# Muddi.net
KiCad netlist of a schematic drawn in EAGLE
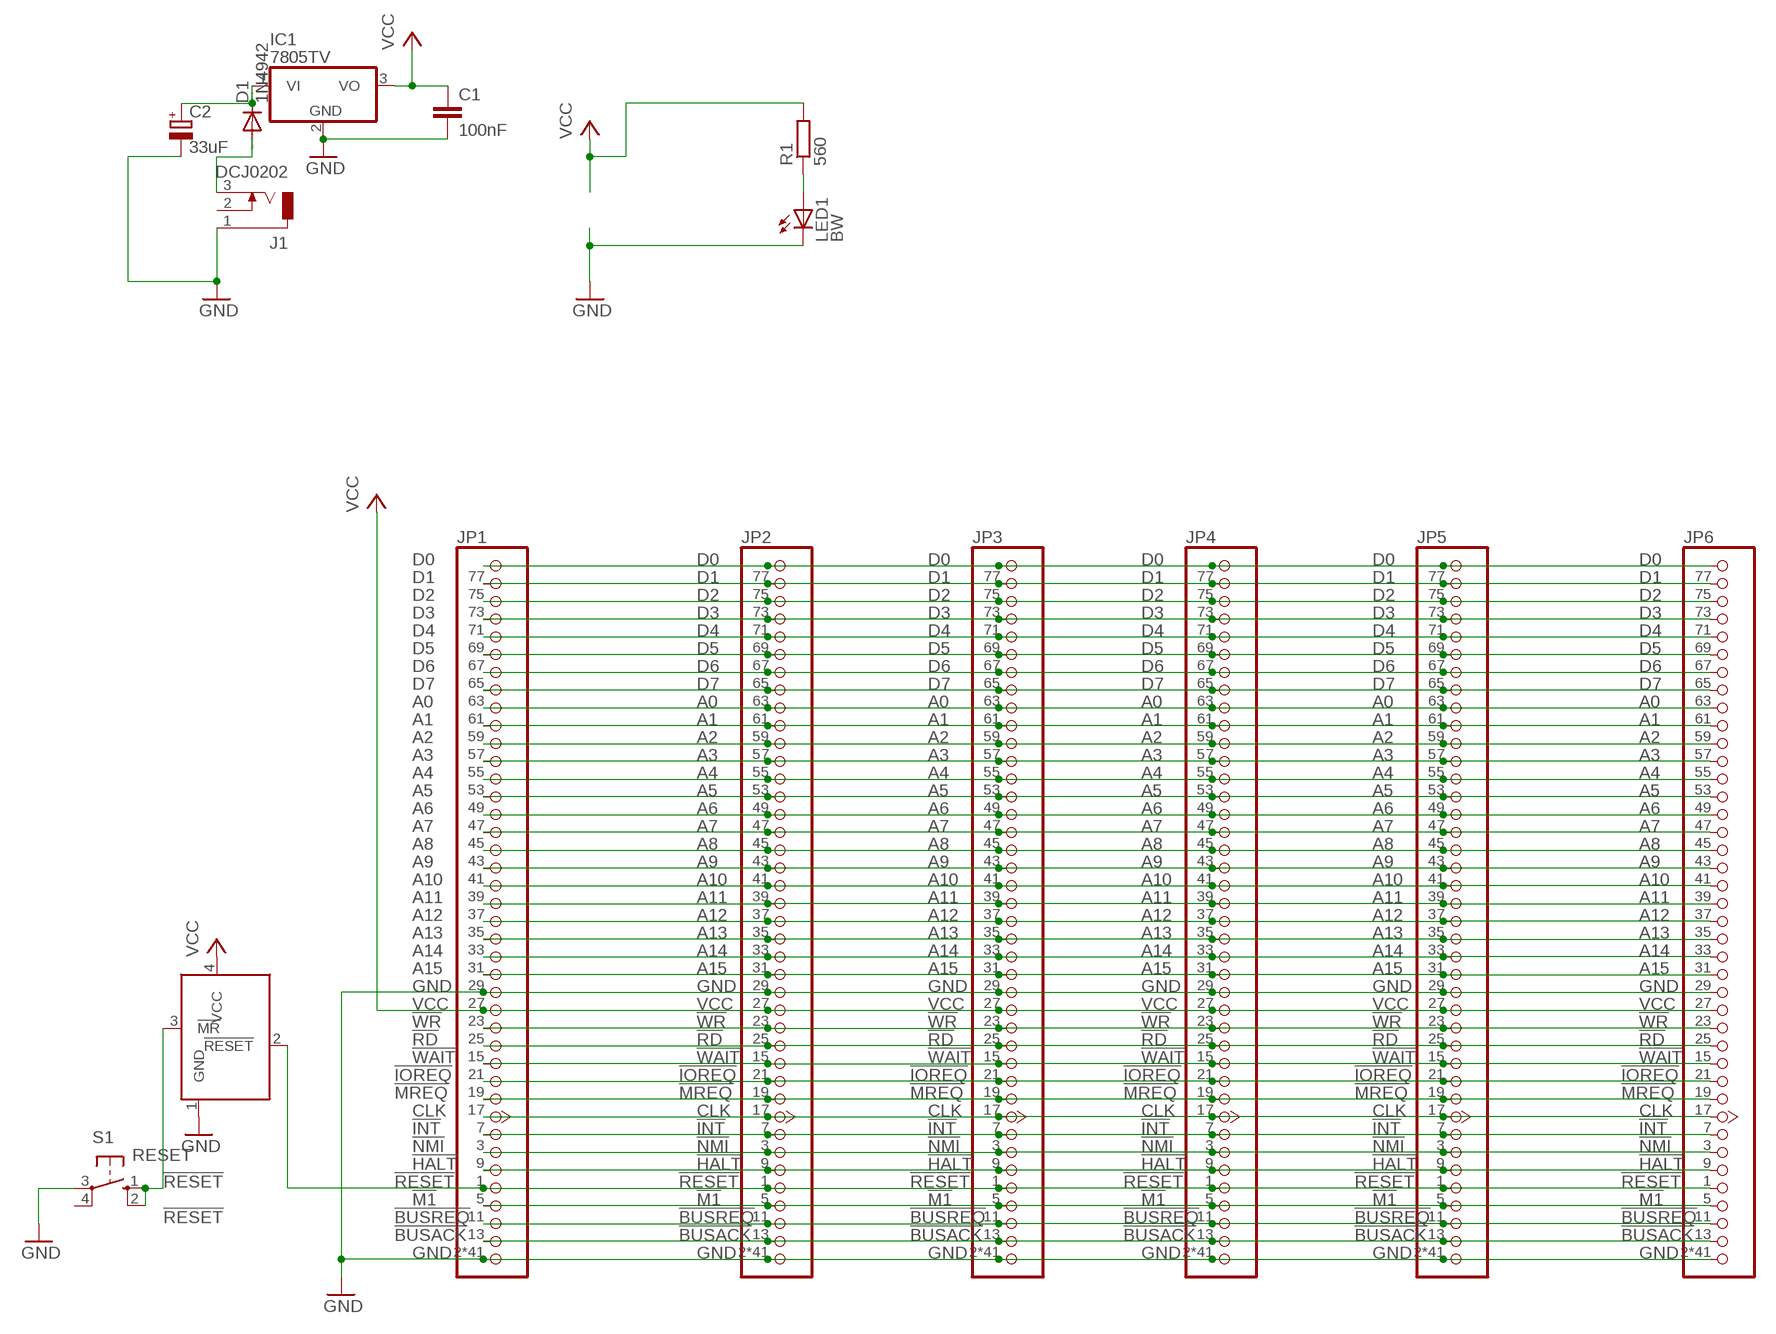
[diagram p0: schematic, sheet 1]

(export (version "E")
  (design (tool "Eeschema 10.0.6"))
  (components
    (comp (ref "C1")
      (value "100nF")
      (footprint "eagle-import:C2.5-2")
      (libsource (lib "eagle-import") (part "C2.5/2"))
    )
    (comp (ref "C2")
      (value "33uF")
      (footprint "eagle-import:E2,5-7")
      (libsource (lib "eagle-import") (part "CPOL-EUE2.5-7"))
    )
    (comp (ref "D1")
      (value "1N4942")
      (footprint "eagle-import:DO41-10")
      (fields (field (name "MF") "ON SEMICONDUCTOR") (field (name "MPN") "1N4935G"))
      (libsource (lib "eagle-import") (part "1N4942"))
    )
    (comp (ref "IC1")
      (value "7805TV")
      (footprint "eagle-import:TO220V")
      (libsource (lib "eagle-import") (part "78TV05"))
    )
    (comp (ref "J1")
      (value "DCJ0202")
      (footprint "eagle-import:DCJ0202")
      (libsource (lib "eagle-import") (part "DCJ0202"))
    )
    (comp (ref "JP1")
      (value "JEANNECTOR_57102-F08-25")
      (footprint "eagle-import:57102-F08-25")
      (libsource (lib "eagle-import") (part "JEANNECTOR_57102-F08-25"))
    )
    (comp (ref "JP2")
      (value "JEANNECTOR_57102-F08-25")
      (footprint "eagle-import:57102-F08-25")
      (libsource (lib "eagle-import") (part "JEANNECTOR_57102-F08-25"))
    )
    (comp (ref "JP3")
      (value "JEANNECTOR_57102-F08-25")
      (footprint "eagle-import:57102-F08-25")
      (libsource (lib "eagle-import") (part "JEANNECTOR_57102-F08-25"))
    )
    (comp (ref "JP4")
      (value "JEANNECTOR_57102-F08-25")
      (footprint "eagle-import:57102-F08-25")
      (libsource (lib "eagle-import") (part "JEANNECTOR_57102-F08-25"))
    )
    (comp (ref "JP5")
      (value "JEANNECTOR_57102-F08-25")
      (footprint "eagle-import:57102-F08-25")
      (libsource (lib "eagle-import") (part "JEANNECTOR_57102-F08-25"))
    )
    (comp (ref "JP6")
      (value "JEANNECTOR_57102-F08-25")
      (footprint "eagle-import:57102-F08-25")
      (libsource (lib "eagle-import") (part "JEANNECTOR_57102-F08-25"))
    )
    (comp (ref "LED1")
      (value "BW")
      (footprint "eagle-import:LED5MM")
      (libsource (lib "eagle-import") (part "LED5MM"))
    )
    (comp (ref "MAX811")
      (value "MAX811")
      (footprint "eagle-import:SOT143")
      (libsource (lib "eagle-import") (part "MAX811"))
    )
    (comp (ref "R1")
      (value "560")
      (footprint "eagle-import:0207_2V")
      (libsource (lib "eagle-import") (part "R-EU_0207/2V"))
    )
    (comp (ref "S1")
      (value "RESET")
      (footprint "eagle-import:B3F-10XX")
      (fields (field (name "MPN") "B3F-1000") (field (name "MF") "OMRON ELECTRONIC COMPONENTS"))
      (libsource (lib "eagle-import") (part "10-XX"))
    )
  )
  (nets
    (net (code "1") (name "/~{RESET}") (class "Default")
      (node (ref "MAX811") (pin "3") (pinfunction "~{MR}_3") (pintype "input"))
      (node (ref "S1") (pin "1") (pinfunction "S_1") (pintype "passive"))
      (node (ref "S1") (pin "2") (pinfunction "S1_2") (pintype "passive"))
    )
    (net (code "2") (name "GND") (class "Default")
      (node (ref "C1") (pin "2") (pinfunction "2_2") (pintype "passive"))
      (node (ref "C2") (pin "-") (pinfunction "-_-") (pintype "passive"))
      (node (ref "IC1") (pin "2") (pinfunction "GND_2") (pintype "passive"))
      (node (ref "J1") (pin "1") (pinfunction "1_1") (pintype "passive"))
      (node (ref "JP1") (pin "10") (pinfunction "GND_10") (pintype "power_in"))
      (node (ref "JP1") (pin "12") (pinfunction "GND_12") (pintype "power_in"))
      (node (ref "JP1") (pin "14") (pinfunction "GND_14") (pintype "power_in"))
      (node (ref "JP1") (pin "16") (pinfunction "GND_16") (pintype "power_in"))
      (node (ref "JP1") (pin "18") (pinfunction "GND_18") (pintype "power_in"))
      (node (ref "JP1") (pin "2") (pinfunction "GND_2") (pintype "power_in"))
      (node (ref "JP1") (pin "20") (pinfunction "GND_20") (pintype "power_in"))
      (node (ref "JP1") (pin "22") (pinfunction "GND_22") (pintype "power_in"))
      (node (ref "JP1") (pin "24") (pinfunction "GND_24") (pintype "power_in"))
      (node (ref "JP1") (pin "26") (pinfunction "GND_26") (pintype "power_in"))
      (node (ref "JP1") (pin "28") (pinfunction "GND_28") (pintype "power_in"))
      (node (ref "JP1") (pin "29") (pinfunction "GND_29") (pintype "power_in"))
      (node (ref "JP1") (pin "30") (pinfunction "GND_30") (pintype "power_in"))
      (node (ref "JP1") (pin "32") (pinfunction "GND_32") (pintype "power_in"))
      (node (ref "JP1") (pin "34") (pinfunction "GND_34") (pintype "power_in"))
      (node (ref "JP1") (pin "36") (pinfunction "GND_36") (pintype "power_in"))
      (node (ref "JP1") (pin "38") (pinfunction "GND_38") (pintype "power_in"))
      (node (ref "JP1") (pin "4") (pinfunction "GND_4") (pintype "power_in"))
      (node (ref "JP1") (pin "40") (pinfunction "GND_40") (pintype "power_in"))
      (node (ref "JP1") (pin "42") (pinfunction "GND_42") (pintype "power_in"))
      (node (ref "JP1") (pin "44") (pinfunction "GND_44") (pintype "power_in"))
      (node (ref "JP1") (pin "46") (pinfunction "GND_46") (pintype "power_in"))
      (node (ref "JP1") (pin "48") (pinfunction "GND_48") (pintype "power_in"))
      (node (ref "JP1") (pin "50") (pinfunction "GND_50") (pintype "power_in"))
      (node (ref "JP1") (pin "51") (pinfunction "GND_51") (pintype "power_in"))
      (node (ref "JP1") (pin "52") (pinfunction "GND_52") (pintype "power_in"))
      (node (ref "JP1") (pin "54") (pinfunction "GND_54") (pintype "power_in"))
      (node (ref "JP1") (pin "56") (pinfunction "GND_56") (pintype "power_in"))
      (node (ref "JP1") (pin "58") (pinfunction "GND_58") (pintype "power_in"))
      (node (ref "JP1") (pin "6") (pinfunction "GND_6") (pintype "power_in"))
      (node (ref "JP1") (pin "60") (pinfunction "GND_60") (pintype "power_in"))
      (node (ref "JP1") (pin "62") (pinfunction "GND_62") (pintype "power_in"))
      (node (ref "JP1") (pin "64") (pinfunction "GND_64") (pintype "power_in"))
      (node (ref "JP1") (pin "66") (pinfunction "GND_66") (pintype "power_in"))
      (node (ref "JP1") (pin "68") (pinfunction "GND_68") (pintype "power_in"))
      (node (ref "JP1") (pin "70") (pinfunction "GND_70") (pintype "power_in"))
      (node (ref "JP1") (pin "72") (pinfunction "GND_72") (pintype "power_in"))
      (node (ref "JP1") (pin "74") (pinfunction "GND_74") (pintype "power_in"))
      (node (ref "JP1") (pin "76") (pinfunction "GND_76") (pintype "power_in"))
      (node (ref "JP1") (pin "78") (pinfunction "GND_78") (pintype "power_in"))
      (node (ref "JP1") (pin "8") (pinfunction "GND_8") (pintype "power_in"))
      (node (ref "JP1") (pin "80") (pinfunction "GND_80") (pintype "power_in"))
      (node (ref "JP2") (pin "10") (pinfunction "GND_10") (pintype "power_in"))
      (node (ref "JP2") (pin "12") (pinfunction "GND_12") (pintype "power_in"))
      (node (ref "JP2") (pin "14") (pinfunction "GND_14") (pintype "power_in"))
      (node (ref "JP2") (pin "16") (pinfunction "GND_16") (pintype "power_in"))
      (node (ref "JP2") (pin "18") (pinfunction "GND_18") (pintype "power_in"))
      (node (ref "JP2") (pin "2") (pinfunction "GND_2") (pintype "power_in"))
      (node (ref "JP2") (pin "20") (pinfunction "GND_20") (pintype "power_in"))
      (node (ref "JP2") (pin "22") (pinfunction "GND_22") (pintype "power_in"))
      (node (ref "JP2") (pin "24") (pinfunction "GND_24") (pintype "power_in"))
      (node (ref "JP2") (pin "26") (pinfunction "GND_26") (pintype "power_in"))
      (node (ref "JP2") (pin "28") (pinfunction "GND_28") (pintype "power_in"))
      (node (ref "JP2") (pin "29") (pinfunction "GND_29") (pintype "power_in"))
      (node (ref "JP2") (pin "30") (pinfunction "GND_30") (pintype "power_in"))
      (node (ref "JP2") (pin "32") (pinfunction "GND_32") (pintype "power_in"))
      (node (ref "JP2") (pin "34") (pinfunction "GND_34") (pintype "power_in"))
      (node (ref "JP2") (pin "36") (pinfunction "GND_36") (pintype "power_in"))
      (node (ref "JP2") (pin "38") (pinfunction "GND_38") (pintype "power_in"))
      (node (ref "JP2") (pin "4") (pinfunction "GND_4") (pintype "power_in"))
      (node (ref "JP2") (pin "40") (pinfunction "GND_40") (pintype "power_in"))
      (node (ref "JP2") (pin "42") (pinfunction "GND_42") (pintype "power_in"))
      (node (ref "JP2") (pin "44") (pinfunction "GND_44") (pintype "power_in"))
      (node (ref "JP2") (pin "46") (pinfunction "GND_46") (pintype "power_in"))
      (node (ref "JP2") (pin "48") (pinfunction "GND_48") (pintype "power_in"))
      (node (ref "JP2") (pin "50") (pinfunction "GND_50") (pintype "power_in"))
      (node (ref "JP2") (pin "51") (pinfunction "GND_51") (pintype "power_in"))
      (node (ref "JP2") (pin "52") (pinfunction "GND_52") (pintype "power_in"))
      (node (ref "JP2") (pin "54") (pinfunction "GND_54") (pintype "power_in"))
      (node (ref "JP2") (pin "56") (pinfunction "GND_56") (pintype "power_in"))
      (node (ref "JP2") (pin "58") (pinfunction "GND_58") (pintype "power_in"))
      (node (ref "JP2") (pin "6") (pinfunction "GND_6") (pintype "power_in"))
      (node (ref "JP2") (pin "60") (pinfunction "GND_60") (pintype "power_in"))
      (node (ref "JP2") (pin "62") (pinfunction "GND_62") (pintype "power_in"))
      (node (ref "JP2") (pin "64") (pinfunction "GND_64") (pintype "power_in"))
      (node (ref "JP2") (pin "66") (pinfunction "GND_66") (pintype "power_in"))
      (node (ref "JP2") (pin "68") (pinfunction "GND_68") (pintype "power_in"))
      (node (ref "JP2") (pin "70") (pinfunction "GND_70") (pintype "power_in"))
      (node (ref "JP2") (pin "72") (pinfunction "GND_72") (pintype "power_in"))
      (node (ref "JP2") (pin "74") (pinfunction "GND_74") (pintype "power_in"))
      (node (ref "JP2") (pin "76") (pinfunction "GND_76") (pintype "power_in"))
      (node (ref "JP2") (pin "78") (pinfunction "GND_78") (pintype "power_in"))
      (node (ref "JP2") (pin "8") (pinfunction "GND_8") (pintype "power_in"))
      (node (ref "JP2") (pin "80") (pinfunction "GND_80") (pintype "power_in"))
      (node (ref "JP3") (pin "10") (pinfunction "GND_10") (pintype "power_in"))
      (node (ref "JP3") (pin "12") (pinfunction "GND_12") (pintype "power_in"))
      (node (ref "JP3") (pin "14") (pinfunction "GND_14") (pintype "power_in"))
      (node (ref "JP3") (pin "16") (pinfunction "GND_16") (pintype "power_in"))
      (node (ref "JP3") (pin "18") (pinfunction "GND_18") (pintype "power_in"))
      (node (ref "JP3") (pin "2") (pinfunction "GND_2") (pintype "power_in"))
      (node (ref "JP3") (pin "20") (pinfunction "GND_20") (pintype "power_in"))
      (node (ref "JP3") (pin "22") (pinfunction "GND_22") (pintype "power_in"))
      (node (ref "JP3") (pin "24") (pinfunction "GND_24") (pintype "power_in"))
      (node (ref "JP3") (pin "26") (pinfunction "GND_26") (pintype "power_in"))
      (node (ref "JP3") (pin "28") (pinfunction "GND_28") (pintype "power_in"))
      (node (ref "JP3") (pin "29") (pinfunction "GND_29") (pintype "power_in"))
      (node (ref "JP3") (pin "30") (pinfunction "GND_30") (pintype "power_in"))
      (node (ref "JP3") (pin "32") (pinfunction "GND_32") (pintype "power_in"))
      (node (ref "JP3") (pin "34") (pinfunction "GND_34") (pintype "power_in"))
      (node (ref "JP3") (pin "36") (pinfunction "GND_36") (pintype "power_in"))
      (node (ref "JP3") (pin "38") (pinfunction "GND_38") (pintype "power_in"))
      (node (ref "JP3") (pin "4") (pinfunction "GND_4") (pintype "power_in"))
      (node (ref "JP3") (pin "40") (pinfunction "GND_40") (pintype "power_in"))
      (node (ref "JP3") (pin "42") (pinfunction "GND_42") (pintype "power_in"))
      (node (ref "JP3") (pin "44") (pinfunction "GND_44") (pintype "power_in"))
      (node (ref "JP3") (pin "46") (pinfunction "GND_46") (pintype "power_in"))
      (node (ref "JP3") (pin "48") (pinfunction "GND_48") (pintype "power_in"))
      (node (ref "JP3") (pin "50") (pinfunction "GND_50") (pintype "power_in"))
      (node (ref "JP3") (pin "51") (pinfunction "GND_51") (pintype "power_in"))
      (node (ref "JP3") (pin "52") (pinfunction "GND_52") (pintype "power_in"))
      (node (ref "JP3") (pin "54") (pinfunction "GND_54") (pintype "power_in"))
      (node (ref "JP3") (pin "56") (pinfunction "GND_56") (pintype "power_in"))
      (node (ref "JP3") (pin "58") (pinfunction "GND_58") (pintype "power_in"))
      (node (ref "JP3") (pin "6") (pinfunction "GND_6") (pintype "power_in"))
      (node (ref "JP3") (pin "60") (pinfunction "GND_60") (pintype "power_in"))
      (node (ref "JP3") (pin "62") (pinfunction "GND_62") (pintype "power_in"))
      (node (ref "JP3") (pin "64") (pinfunction "GND_64") (pintype "power_in"))
      (node (ref "JP3") (pin "66") (pinfunction "GND_66") (pintype "power_in"))
      (node (ref "JP3") (pin "68") (pinfunction "GND_68") (pintype "power_in"))
      (node (ref "JP3") (pin "70") (pinfunction "GND_70") (pintype "power_in"))
      (node (ref "JP3") (pin "72") (pinfunction "GND_72") (pintype "power_in"))
      (node (ref "JP3") (pin "74") (pinfunction "GND_74") (pintype "power_in"))
      (node (ref "JP3") (pin "76") (pinfunction "GND_76") (pintype "power_in"))
      (node (ref "JP3") (pin "78") (pinfunction "GND_78") (pintype "power_in"))
      (node (ref "JP3") (pin "8") (pinfunction "GND_8") (pintype "power_in"))
      (node (ref "JP3") (pin "80") (pinfunction "GND_80") (pintype "power_in"))
      (node (ref "JP4") (pin "10") (pinfunction "GND_10") (pintype "power_in"))
      (node (ref "JP4") (pin "12") (pinfunction "GND_12") (pintype "power_in"))
      (node (ref "JP4") (pin "14") (pinfunction "GND_14") (pintype "power_in"))
      (node (ref "JP4") (pin "16") (pinfunction "GND_16") (pintype "power_in"))
      (node (ref "JP4") (pin "18") (pinfunction "GND_18") (pintype "power_in"))
      (node (ref "JP4") (pin "2") (pinfunction "GND_2") (pintype "power_in"))
      (node (ref "JP4") (pin "20") (pinfunction "GND_20") (pintype "power_in"))
      (node (ref "JP4") (pin "22") (pinfunction "GND_22") (pintype "power_in"))
      (node (ref "JP4") (pin "24") (pinfunction "GND_24") (pintype "power_in"))
      (node (ref "JP4") (pin "26") (pinfunction "GND_26") (pintype "power_in"))
      (node (ref "JP4") (pin "28") (pinfunction "GND_28") (pintype "power_in"))
      (node (ref "JP4") (pin "29") (pinfunction "GND_29") (pintype "power_in"))
      (node (ref "JP4") (pin "30") (pinfunction "GND_30") (pintype "power_in"))
      (node (ref "JP4") (pin "32") (pinfunction "GND_32") (pintype "power_in"))
      (node (ref "JP4") (pin "34") (pinfunction "GND_34") (pintype "power_in"))
      (node (ref "JP4") (pin "36") (pinfunction "GND_36") (pintype "power_in"))
      (node (ref "JP4") (pin "38") (pinfunction "GND_38") (pintype "power_in"))
      (node (ref "JP4") (pin "4") (pinfunction "GND_4") (pintype "power_in"))
      (node (ref "JP4") (pin "40") (pinfunction "GND_40") (pintype "power_in"))
      (node (ref "JP4") (pin "42") (pinfunction "GND_42") (pintype "power_in"))
      (node (ref "JP4") (pin "44") (pinfunction "GND_44") (pintype "power_in"))
      (node (ref "JP4") (pin "46") (pinfunction "GND_46") (pintype "power_in"))
      (node (ref "JP4") (pin "48") (pinfunction "GND_48") (pintype "power_in"))
      (node (ref "JP4") (pin "50") (pinfunction "GND_50") (pintype "power_in"))
      (node (ref "JP4") (pin "51") (pinfunction "GND_51") (pintype "power_in"))
      (node (ref "JP4") (pin "52") (pinfunction "GND_52") (pintype "power_in"))
      (node (ref "JP4") (pin "54") (pinfunction "GND_54") (pintype "power_in"))
      (node (ref "JP4") (pin "56") (pinfunction "GND_56") (pintype "power_in"))
      (node (ref "JP4") (pin "58") (pinfunction "GND_58") (pintype "power_in"))
      (node (ref "JP4") (pin "6") (pinfunction "GND_6") (pintype "power_in"))
      (node (ref "JP4") (pin "60") (pinfunction "GND_60") (pintype "power_in"))
      (node (ref "JP4") (pin "62") (pinfunction "GND_62") (pintype "power_in"))
      (node (ref "JP4") (pin "64") (pinfunction "GND_64") (pintype "power_in"))
      (node (ref "JP4") (pin "66") (pinfunction "GND_66") (pintype "power_in"))
      (node (ref "JP4") (pin "68") (pinfunction "GND_68") (pintype "power_in"))
      (node (ref "JP4") (pin "70") (pinfunction "GND_70") (pintype "power_in"))
      (node (ref "JP4") (pin "72") (pinfunction "GND_72") (pintype "power_in"))
      (node (ref "JP4") (pin "74") (pinfunction "GND_74") (pintype "power_in"))
      (node (ref "JP4") (pin "76") (pinfunction "GND_76") (pintype "power_in"))
      (node (ref "JP4") (pin "78") (pinfunction "GND_78") (pintype "power_in"))
      (node (ref "JP4") (pin "8") (pinfunction "GND_8") (pintype "power_in"))
      (node (ref "JP4") (pin "80") (pinfunction "GND_80") (pintype "power_in"))
      (node (ref "JP5") (pin "10") (pinfunction "GND_10") (pintype "power_in"))
      (node (ref "JP5") (pin "12") (pinfunction "GND_12") (pintype "power_in"))
      (node (ref "JP5") (pin "14") (pinfunction "GND_14") (pintype "power_in"))
      (node (ref "JP5") (pin "16") (pinfunction "GND_16") (pintype "power_in"))
      (node (ref "JP5") (pin "18") (pinfunction "GND_18") (pintype "power_in"))
      (node (ref "JP5") (pin "2") (pinfunction "GND_2") (pintype "power_in"))
      (node (ref "JP5") (pin "20") (pinfunction "GND_20") (pintype "power_in"))
      (node (ref "JP5") (pin "22") (pinfunction "GND_22") (pintype "power_in"))
      (node (ref "JP5") (pin "24") (pinfunction "GND_24") (pintype "power_in"))
      (node (ref "JP5") (pin "26") (pinfunction "GND_26") (pintype "power_in"))
      (node (ref "JP5") (pin "28") (pinfunction "GND_28") (pintype "power_in"))
      (node (ref "JP5") (pin "29") (pinfunction "GND_29") (pintype "power_in"))
      (node (ref "JP5") (pin "30") (pinfunction "GND_30") (pintype "power_in"))
      (node (ref "JP5") (pin "32") (pinfunction "GND_32") (pintype "power_in"))
      (node (ref "JP5") (pin "34") (pinfunction "GND_34") (pintype "power_in"))
      (node (ref "JP5") (pin "36") (pinfunction "GND_36") (pintype "power_in"))
      (node (ref "JP5") (pin "38") (pinfunction "GND_38") (pintype "power_in"))
      (node (ref "JP5") (pin "4") (pinfunction "GND_4") (pintype "power_in"))
      (node (ref "JP5") (pin "40") (pinfunction "GND_40") (pintype "power_in"))
      (node (ref "JP5") (pin "42") (pinfunction "GND_42") (pintype "power_in"))
      (node (ref "JP5") (pin "44") (pinfunction "GND_44") (pintype "power_in"))
      (node (ref "JP5") (pin "46") (pinfunction "GND_46") (pintype "power_in"))
      (node (ref "JP5") (pin "48") (pinfunction "GND_48") (pintype "power_in"))
      (node (ref "JP5") (pin "50") (pinfunction "GND_50") (pintype "power_in"))
      (node (ref "JP5") (pin "51") (pinfunction "GND_51") (pintype "power_in"))
      (node (ref "JP5") (pin "52") (pinfunction "GND_52") (pintype "power_in"))
      (node (ref "JP5") (pin "54") (pinfunction "GND_54") (pintype "power_in"))
      (node (ref "JP5") (pin "56") (pinfunction "GND_56") (pintype "power_in"))
      (node (ref "JP5") (pin "58") (pinfunction "GND_58") (pintype "power_in"))
      (node (ref "JP5") (pin "6") (pinfunction "GND_6") (pintype "power_in"))
      (node (ref "JP5") (pin "60") (pinfunction "GND_60") (pintype "power_in"))
      (node (ref "JP5") (pin "62") (pinfunction "GND_62") (pintype "power_in"))
      (node (ref "JP5") (pin "64") (pinfunction "GND_64") (pintype "power_in"))
      (node (ref "JP5") (pin "66") (pinfunction "GND_66") (pintype "power_in"))
      (node (ref "JP5") (pin "68") (pinfunction "GND_68") (pintype "power_in"))
      (node (ref "JP5") (pin "70") (pinfunction "GND_70") (pintype "power_in"))
      (node (ref "JP5") (pin "72") (pinfunction "GND_72") (pintype "power_in"))
      (node (ref "JP5") (pin "74") (pinfunction "GND_74") (pintype "power_in"))
      (node (ref "JP5") (pin "76") (pinfunction "GND_76") (pintype "power_in"))
      (node (ref "JP5") (pin "78") (pinfunction "GND_78") (pintype "power_in"))
      (node (ref "JP5") (pin "8") (pinfunction "GND_8") (pintype "power_in"))
      (node (ref "JP5") (pin "80") (pinfunction "GND_80") (pintype "power_in"))
      (node (ref "JP6") (pin "10") (pinfunction "GND_10") (pintype "power_in"))
      (node (ref "JP6") (pin "12") (pinfunction "GND_12") (pintype "power_in"))
      (node (ref "JP6") (pin "14") (pinfunction "GND_14") (pintype "power_in"))
      (node (ref "JP6") (pin "16") (pinfunction "GND_16") (pintype "power_in"))
      (node (ref "JP6") (pin "18") (pinfunction "GND_18") (pintype "power_in"))
      (node (ref "JP6") (pin "2") (pinfunction "GND_2") (pintype "power_in"))
      (node (ref "JP6") (pin "20") (pinfunction "GND_20") (pintype "power_in"))
      (node (ref "JP6") (pin "22") (pinfunction "GND_22") (pintype "power_in"))
      (node (ref "JP6") (pin "24") (pinfunction "GND_24") (pintype "power_in"))
      (node (ref "JP6") (pin "26") (pinfunction "GND_26") (pintype "power_in"))
      (node (ref "JP6") (pin "28") (pinfunction "GND_28") (pintype "power_in"))
      (node (ref "JP6") (pin "29") (pinfunction "GND_29") (pintype "power_in"))
      (node (ref "JP6") (pin "30") (pinfunction "GND_30") (pintype "power_in"))
      (node (ref "JP6") (pin "32") (pinfunction "GND_32") (pintype "power_in"))
      (node (ref "JP6") (pin "34") (pinfunction "GND_34") (pintype "power_in"))
      (node (ref "JP6") (pin "36") (pinfunction "GND_36") (pintype "power_in"))
      (node (ref "JP6") (pin "38") (pinfunction "GND_38") (pintype "power_in"))
      (node (ref "JP6") (pin "4") (pinfunction "GND_4") (pintype "power_in"))
      (node (ref "JP6") (pin "40") (pinfunction "GND_40") (pintype "power_in"))
      (node (ref "JP6") (pin "42") (pinfunction "GND_42") (pintype "power_in"))
      (node (ref "JP6") (pin "44") (pinfunction "GND_44") (pintype "power_in"))
      (node (ref "JP6") (pin "46") (pinfunction "GND_46") (pintype "power_in"))
      (node (ref "JP6") (pin "48") (pinfunction "GND_48") (pintype "power_in"))
      (node (ref "JP6") (pin "50") (pinfunction "GND_50") (pintype "power_in"))
      (node (ref "JP6") (pin "51") (pinfunction "GND_51") (pintype "power_in"))
      (node (ref "JP6") (pin "52") (pinfunction "GND_52") (pintype "power_in"))
      (node (ref "JP6") (pin "54") (pinfunction "GND_54") (pintype "power_in"))
      (node (ref "JP6") (pin "56") (pinfunction "GND_56") (pintype "power_in"))
      (node (ref "JP6") (pin "58") (pinfunction "GND_58") (pintype "power_in"))
      (node (ref "JP6") (pin "6") (pinfunction "GND_6") (pintype "power_in"))
      (node (ref "JP6") (pin "60") (pinfunction "GND_60") (pintype "power_in"))
      (node (ref "JP6") (pin "62") (pinfunction "GND_62") (pintype "power_in"))
      (node (ref "JP6") (pin "64") (pinfunction "GND_64") (pintype "power_in"))
      (node (ref "JP6") (pin "66") (pinfunction "GND_66") (pintype "power_in"))
      (node (ref "JP6") (pin "68") (pinfunction "GND_68") (pintype "power_in"))
      (node (ref "JP6") (pin "70") (pinfunction "GND_70") (pintype "power_in"))
      (node (ref "JP6") (pin "72") (pinfunction "GND_72") (pintype "power_in"))
      (node (ref "JP6") (pin "74") (pinfunction "GND_74") (pintype "power_in"))
      (node (ref "JP6") (pin "76") (pinfunction "GND_76") (pintype "power_in"))
      (node (ref "JP6") (pin "78") (pinfunction "GND_78") (pintype "power_in"))
      (node (ref "JP6") (pin "8") (pinfunction "GND_8") (pintype "power_in"))
      (node (ref "JP6") (pin "80") (pinfunction "GND_80") (pintype "power_in"))
      (node (ref "LED1") (pin "K") (pinfunction "C_K") (pintype "passive"))
      (node (ref "MAX811") (pin "1") (pinfunction "GND_1") (pintype "power_in"))
      (node (ref "S1") (pin "3") (pinfunction "P_3") (pintype "passive"))
    )
    (net (code "3") (name "Net-(D1-PadA)") (class "Default")
      (node (ref "D1") (pin "A") (pinfunction "A_A") (pintype "passive"))
      (node (ref "J1") (pin "3") (pinfunction "3_3") (pintype "passive"))
    )
    (net (code "4") (name "Net-(IC1-VI)") (class "Default")
      (node (ref "C2") (pin "+") (pinfunction "+_+") (pintype "passive"))
      (node (ref "D1") (pin "C") (pinfunction "C_C") (pintype "passive"))
      (node (ref "IC1") (pin "1") (pinfunction "VI_1") (pintype "input"))
    )
    (net (code "5") (name "Net-(JP1-A0)") (class "Default")
      (node (ref "JP1") (pin "63") (pinfunction "A0_63") (pintype "bidirectional"))
      (node (ref "JP2") (pin "63") (pinfunction "A0_63") (pintype "bidirectional"))
      (node (ref "JP3") (pin "63") (pinfunction "A0_63") (pintype "bidirectional"))
      (node (ref "JP4") (pin "63") (pinfunction "A0_63") (pintype "bidirectional"))
      (node (ref "JP5") (pin "63") (pinfunction "A0_63") (pintype "bidirectional"))
      (node (ref "JP6") (pin "63") (pinfunction "A0_63") (pintype "bidirectional"))
    )
    (net (code "6") (name "Net-(JP1-A1)") (class "Default")
      (node (ref "JP1") (pin "61") (pinfunction "A1_61") (pintype "bidirectional"))
      (node (ref "JP2") (pin "61") (pinfunction "A1_61") (pintype "bidirectional"))
      (node (ref "JP3") (pin "61") (pinfunction "A1_61") (pintype "bidirectional"))
      (node (ref "JP4") (pin "61") (pinfunction "A1_61") (pintype "bidirectional"))
      (node (ref "JP5") (pin "61") (pinfunction "A1_61") (pintype "bidirectional"))
      (node (ref "JP6") (pin "61") (pinfunction "A1_61") (pintype "bidirectional"))
    )
    (net (code "7") (name "Net-(JP1-A2)") (class "Default")
      (node (ref "JP1") (pin "59") (pinfunction "A2_59") (pintype "bidirectional"))
      (node (ref "JP2") (pin "59") (pinfunction "A2_59") (pintype "bidirectional"))
      (node (ref "JP3") (pin "59") (pinfunction "A2_59") (pintype "bidirectional"))
      (node (ref "JP4") (pin "59") (pinfunction "A2_59") (pintype "bidirectional"))
      (node (ref "JP5") (pin "59") (pinfunction "A2_59") (pintype "bidirectional"))
      (node (ref "JP6") (pin "59") (pinfunction "A2_59") (pintype "bidirectional"))
    )
    (net (code "8") (name "Net-(JP1-A3)") (class "Default")
      (node (ref "JP1") (pin "57") (pinfunction "A3_57") (pintype "bidirectional"))
      (node (ref "JP2") (pin "57") (pinfunction "A3_57") (pintype "bidirectional"))
      (node (ref "JP3") (pin "57") (pinfunction "A3_57") (pintype "bidirectional"))
      (node (ref "JP4") (pin "57") (pinfunction "A3_57") (pintype "bidirectional"))
      (node (ref "JP5") (pin "57") (pinfunction "A3_57") (pintype "bidirectional"))
      (node (ref "JP6") (pin "57") (pinfunction "A3_57") (pintype "bidirectional"))
    )
    (net (code "9") (name "Net-(JP1-A4)") (class "Default")
      (node (ref "JP1") (pin "55") (pinfunction "A4_55") (pintype "bidirectional"))
      (node (ref "JP2") (pin "55") (pinfunction "A4_55") (pintype "bidirectional"))
      (node (ref "JP3") (pin "55") (pinfunction "A4_55") (pintype "bidirectional"))
      (node (ref "JP4") (pin "55") (pinfunction "A4_55") (pintype "bidirectional"))
      (node (ref "JP5") (pin "55") (pinfunction "A4_55") (pintype "bidirectional"))
      (node (ref "JP6") (pin "55") (pinfunction "A4_55") (pintype "bidirectional"))
    )
    (net (code "10") (name "Net-(JP1-A5)") (class "Default")
      (node (ref "JP1") (pin "53") (pinfunction "A5_53") (pintype "bidirectional"))
      (node (ref "JP2") (pin "53") (pinfunction "A5_53") (pintype "bidirectional"))
      (node (ref "JP3") (pin "53") (pinfunction "A5_53") (pintype "bidirectional"))
      (node (ref "JP4") (pin "53") (pinfunction "A5_53") (pintype "bidirectional"))
      (node (ref "JP5") (pin "53") (pinfunction "A5_53") (pintype "bidirectional"))
      (node (ref "JP6") (pin "53") (pinfunction "A5_53") (pintype "bidirectional"))
    )
    (net (code "11") (name "Net-(JP1-A6)") (class "Default")
      (node (ref "JP1") (pin "49") (pinfunction "A6_49") (pintype "bidirectional"))
      (node (ref "JP2") (pin "49") (pinfunction "A6_49") (pintype "bidirectional"))
      (node (ref "JP3") (pin "49") (pinfunction "A6_49") (pintype "bidirectional"))
      (node (ref "JP4") (pin "49") (pinfunction "A6_49") (pintype "bidirectional"))
      (node (ref "JP5") (pin "49") (pinfunction "A6_49") (pintype "bidirectional"))
      (node (ref "JP6") (pin "49") (pinfunction "A6_49") (pintype "bidirectional"))
    )
    (net (code "12") (name "Net-(JP1-A7)") (class "Default")
      (node (ref "JP1") (pin "47") (pinfunction "A7_47") (pintype "bidirectional"))
      (node (ref "JP2") (pin "47") (pinfunction "A7_47") (pintype "bidirectional"))
      (node (ref "JP3") (pin "47") (pinfunction "A7_47") (pintype "bidirectional"))
      (node (ref "JP4") (pin "47") (pinfunction "A7_47") (pintype "bidirectional"))
      (node (ref "JP5") (pin "47") (pinfunction "A7_47") (pintype "bidirectional"))
      (node (ref "JP6") (pin "47") (pinfunction "A7_47") (pintype "bidirectional"))
    )
    (net (code "13") (name "Net-(JP1-A8)") (class "Default")
      (node (ref "JP1") (pin "45") (pinfunction "A8_45") (pintype "bidirectional"))
      (node (ref "JP2") (pin "45") (pinfunction "A8_45") (pintype "bidirectional"))
      (node (ref "JP3") (pin "45") (pinfunction "A8_45") (pintype "bidirectional"))
      (node (ref "JP4") (pin "45") (pinfunction "A8_45") (pintype "bidirectional"))
      (node (ref "JP5") (pin "45") (pinfunction "A8_45") (pintype "bidirectional"))
      (node (ref "JP6") (pin "45") (pinfunction "A8_45") (pintype "bidirectional"))
    )
    (net (code "14") (name "Net-(JP1-A9)") (class "Default")
      (node (ref "JP1") (pin "43") (pinfunction "A9_43") (pintype "bidirectional"))
      (node (ref "JP2") (pin "43") (pinfunction "A9_43") (pintype "bidirectional"))
      (node (ref "JP3") (pin "43") (pinfunction "A9_43") (pintype "bidirectional"))
      (node (ref "JP4") (pin "43") (pinfunction "A9_43") (pintype "bidirectional"))
      (node (ref "JP5") (pin "43") (pinfunction "A9_43") (pintype "bidirectional"))
      (node (ref "JP6") (pin "43") (pinfunction "A9_43") (pintype "bidirectional"))
    )
    (net (code "15") (name "Net-(JP1-A10)") (class "Default")
      (node (ref "JP1") (pin "41") (pinfunction "A10_41") (pintype "bidirectional"))
      (node (ref "JP2") (pin "41") (pinfunction "A10_41") (pintype "bidirectional"))
      (node (ref "JP3") (pin "41") (pinfunction "A10_41") (pintype "bidirectional"))
      (node (ref "JP4") (pin "41") (pinfunction "A10_41") (pintype "bidirectional"))
      (node (ref "JP5") (pin "41") (pinfunction "A10_41") (pintype "bidirectional"))
      (node (ref "JP6") (pin "41") (pinfunction "A10_41") (pintype "bidirectional"))
    )
    (net (code "16") (name "Net-(JP1-A11)") (class "Default")
      (node (ref "JP1") (pin "39") (pinfunction "A11_39") (pintype "bidirectional"))
      (node (ref "JP2") (pin "39") (pinfunction "A11_39") (pintype "bidirectional"))
      (node (ref "JP3") (pin "39") (pinfunction "A11_39") (pintype "bidirectional"))
      (node (ref "JP4") (pin "39") (pinfunction "A11_39") (pintype "bidirectional"))
      (node (ref "JP5") (pin "39") (pinfunction "A11_39") (pintype "bidirectional"))
      (node (ref "JP6") (pin "39") (pinfunction "A11_39") (pintype "bidirectional"))
    )
    (net (code "17") (name "Net-(JP1-A12)") (class "Default")
      (node (ref "JP1") (pin "37") (pinfunction "A12_37") (pintype "bidirectional"))
      (node (ref "JP2") (pin "37") (pinfunction "A12_37") (pintype "bidirectional"))
      (node (ref "JP3") (pin "37") (pinfunction "A12_37") (pintype "bidirectional"))
      (node (ref "JP4") (pin "37") (pinfunction "A12_37") (pintype "bidirectional"))
      (node (ref "JP5") (pin "37") (pinfunction "A12_37") (pintype "bidirectional"))
      (node (ref "JP6") (pin "37") (pinfunction "A12_37") (pintype "bidirectional"))
    )
    (net (code "18") (name "Net-(JP1-A13)") (class "Default")
      (node (ref "JP1") (pin "35") (pinfunction "A13_35") (pintype "bidirectional"))
      (node (ref "JP2") (pin "35") (pinfunction "A13_35") (pintype "bidirectional"))
      (node (ref "JP3") (pin "35") (pinfunction "A13_35") (pintype "bidirectional"))
      (node (ref "JP4") (pin "35") (pinfunction "A13_35") (pintype "bidirectional"))
      (node (ref "JP5") (pin "35") (pinfunction "A13_35") (pintype "bidirectional"))
      (node (ref "JP6") (pin "35") (pinfunction "A13_35") (pintype "bidirectional"))
    )
    (net (code "19") (name "Net-(JP1-A14)") (class "Default")
      (node (ref "JP1") (pin "33") (pinfunction "A14_33") (pintype "bidirectional"))
      (node (ref "JP2") (pin "33") (pinfunction "A14_33") (pintype "bidirectional"))
      (node (ref "JP3") (pin "33") (pinfunction "A14_33") (pintype "bidirectional"))
      (node (ref "JP4") (pin "33") (pinfunction "A14_33") (pintype "bidirectional"))
      (node (ref "JP5") (pin "33") (pinfunction "A14_33") (pintype "bidirectional"))
      (node (ref "JP6") (pin "33") (pinfunction "A14_33") (pintype "bidirectional"))
    )
    (net (code "20") (name "Net-(JP1-A15)") (class "Default")
      (node (ref "JP1") (pin "31") (pinfunction "A15_31") (pintype "bidirectional"))
      (node (ref "JP2") (pin "31") (pinfunction "A15_31") (pintype "bidirectional"))
      (node (ref "JP3") (pin "31") (pinfunction "A15_31") (pintype "bidirectional"))
      (node (ref "JP4") (pin "31") (pinfunction "A15_31") (pintype "bidirectional"))
      (node (ref "JP5") (pin "31") (pinfunction "A15_31") (pintype "bidirectional"))
      (node (ref "JP6") (pin "31") (pinfunction "A15_31") (pintype "bidirectional"))
    )
    (net (code "21") (name "Net-(JP1-CLK)") (class "Default")
      (node (ref "JP1") (pin "17") (pinfunction "CLK_17") (pintype "passive"))
      (node (ref "JP2") (pin "17") (pinfunction "CLK_17") (pintype "passive"))
      (node (ref "JP3") (pin "17") (pinfunction "CLK_17") (pintype "passive"))
      (node (ref "JP4") (pin "17") (pinfunction "CLK_17") (pintype "passive"))
      (node (ref "JP5") (pin "17") (pinfunction "CLK_17") (pintype "passive"))
      (node (ref "JP6") (pin "17") (pinfunction "CLK_17") (pintype "passive"))
    )
    (net (code "22") (name "Net-(JP1-D0)") (class "Default")
      (node (ref "JP1") (pin "79") (pinfunction "D0_79") (pintype "bidirectional"))
      (node (ref "JP2") (pin "79") (pinfunction "D0_79") (pintype "bidirectional"))
      (node (ref "JP3") (pin "79") (pinfunction "D0_79") (pintype "bidirectional"))
      (node (ref "JP4") (pin "79") (pinfunction "D0_79") (pintype "bidirectional"))
      (node (ref "JP5") (pin "79") (pinfunction "D0_79") (pintype "bidirectional"))
      (node (ref "JP6") (pin "79") (pinfunction "D0_79") (pintype "bidirectional"))
    )
    (net (code "23") (name "Net-(JP1-D1)") (class "Default")
      (node (ref "JP1") (pin "77") (pinfunction "D1_77") (pintype "bidirectional"))
      (node (ref "JP2") (pin "77") (pinfunction "D1_77") (pintype "bidirectional"))
      (node (ref "JP3") (pin "77") (pinfunction "D1_77") (pintype "bidirectional"))
      (node (ref "JP4") (pin "77") (pinfunction "D1_77") (pintype "bidirectional"))
      (node (ref "JP5") (pin "77") (pinfunction "D1_77") (pintype "bidirectional"))
      (node (ref "JP6") (pin "77") (pinfunction "D1_77") (pintype "bidirectional"))
    )
    (net (code "24") (name "Net-(JP1-D2)") (class "Default")
      (node (ref "JP1") (pin "75") (pinfunction "D2_75") (pintype "bidirectional"))
      (node (ref "JP2") (pin "75") (pinfunction "D2_75") (pintype "bidirectional"))
      (node (ref "JP3") (pin "75") (pinfunction "D2_75") (pintype "bidirectional"))
      (node (ref "JP4") (pin "75") (pinfunction "D2_75") (pintype "bidirectional"))
      (node (ref "JP5") (pin "75") (pinfunction "D2_75") (pintype "bidirectional"))
      (node (ref "JP6") (pin "75") (pinfunction "D2_75") (pintype "bidirectional"))
    )
    (net (code "25") (name "Net-(JP1-D3)") (class "Default")
      (node (ref "JP1") (pin "73") (pinfunction "D3_73") (pintype "bidirectional"))
      (node (ref "JP2") (pin "73") (pinfunction "D3_73") (pintype "bidirectional"))
      (node (ref "JP3") (pin "73") (pinfunction "D3_73") (pintype "bidirectional"))
      (node (ref "JP4") (pin "73") (pinfunction "D3_73") (pintype "bidirectional"))
      (node (ref "JP5") (pin "73") (pinfunction "D3_73") (pintype "bidirectional"))
      (node (ref "JP6") (pin "73") (pinfunction "D3_73") (pintype "bidirectional"))
    )
    (net (code "26") (name "Net-(JP1-D4)") (class "Default")
      (node (ref "JP1") (pin "71") (pinfunction "D4_71") (pintype "bidirectional"))
      (node (ref "JP2") (pin "71") (pinfunction "D4_71") (pintype "bidirectional"))
      (node (ref "JP3") (pin "71") (pinfunction "D4_71") (pintype "bidirectional"))
      (node (ref "JP4") (pin "71") (pinfunction "D4_71") (pintype "bidirectional"))
      (node (ref "JP5") (pin "71") (pinfunction "D4_71") (pintype "bidirectional"))
      (node (ref "JP6") (pin "71") (pinfunction "D4_71") (pintype "bidirectional"))
    )
    (net (code "27") (name "Net-(JP1-D5)") (class "Default")
      (node (ref "JP1") (pin "69") (pinfunction "D5_69") (pintype "bidirectional"))
      (node (ref "JP2") (pin "69") (pinfunction "D5_69") (pintype "bidirectional"))
      (node (ref "JP3") (pin "69") (pinfunction "D5_69") (pintype "bidirectional"))
      (node (ref "JP4") (pin "69") (pinfunction "D5_69") (pintype "bidirectional"))
      (node (ref "JP5") (pin "69") (pinfunction "D5_69") (pintype "bidirectional"))
      (node (ref "JP6") (pin "69") (pinfunction "D5_69") (pintype "bidirectional"))
    )
    (net (code "28") (name "Net-(JP1-D6)") (class "Default")
      (node (ref "JP1") (pin "67") (pinfunction "D6_67") (pintype "bidirectional"))
      (node (ref "JP2") (pin "67") (pinfunction "D6_67") (pintype "bidirectional"))
      (node (ref "JP3") (pin "67") (pinfunction "D6_67") (pintype "bidirectional"))
      (node (ref "JP4") (pin "67") (pinfunction "D6_67") (pintype "bidirectional"))
      (node (ref "JP5") (pin "67") (pinfunction "D6_67") (pintype "bidirectional"))
      (node (ref "JP6") (pin "67") (pinfunction "D6_67") (pintype "bidirectional"))
    )
    (net (code "29") (name "Net-(JP1-D7)") (class "Default")
      (node (ref "JP1") (pin "65") (pinfunction "D7_65") (pintype "bidirectional"))
      (node (ref "JP2") (pin "65") (pinfunction "D7_65") (pintype "bidirectional"))
      (node (ref "JP3") (pin "65") (pinfunction "D7_65") (pintype "bidirectional"))
      (node (ref "JP4") (pin "65") (pinfunction "D7_65") (pintype "bidirectional"))
      (node (ref "JP5") (pin "65") (pinfunction "D7_65") (pintype "bidirectional"))
      (node (ref "JP6") (pin "65") (pinfunction "D7_65") (pintype "bidirectional"))
    )
    (net (code "30") (name "Net-(JP1-~{BUSACK})") (class "Default")
      (node (ref "JP1") (pin "13") (pinfunction "~{BUSACK}_13") (pintype "input"))
      (node (ref "JP2") (pin "13") (pinfunction "~{BUSACK}_13") (pintype "input"))
      (node (ref "JP3") (pin "13") (pinfunction "~{BUSACK}_13") (pintype "input"))
      (node (ref "JP4") (pin "13") (pinfunction "~{BUSACK}_13") (pintype "input"))
      (node (ref "JP5") (pin "13") (pinfunction "~{BUSACK}_13") (pintype "input"))
      (node (ref "JP6") (pin "13") (pinfunction "~{BUSACK}_13") (pintype "input"))
    )
    (net (code "31") (name "Net-(JP1-~{BUSRQ})") (class "Default")
      (node (ref "JP1") (pin "11") (pinfunction "~{BUSRQ}_11") (pintype "output"))
      (node (ref "JP2") (pin "11") (pinfunction "~{BUSRQ}_11") (pintype "output"))
      (node (ref "JP3") (pin "11") (pinfunction "~{BUSRQ}_11") (pintype "output"))
      (node (ref "JP4") (pin "11") (pinfunction "~{BUSRQ}_11") (pintype "output"))
      (node (ref "JP5") (pin "11") (pinfunction "~{BUSRQ}_11") (pintype "output"))
      (node (ref "JP6") (pin "11") (pinfunction "~{BUSRQ}_11") (pintype "output"))
    )
    (net (code "32") (name "Net-(JP1-~{HALT})") (class "Default")
      (node (ref "JP1") (pin "9") (pinfunction "~{HALT}_9") (pintype "input"))
      (node (ref "JP2") (pin "9") (pinfunction "~{HALT}_9") (pintype "input"))
      (node (ref "JP3") (pin "9") (pinfunction "~{HALT}_9") (pintype "input"))
      (node (ref "JP4") (pin "9") (pinfunction "~{HALT}_9") (pintype "input"))
      (node (ref "JP5") (pin "9") (pinfunction "~{HALT}_9") (pintype "input"))
      (node (ref "JP6") (pin "9") (pinfunction "~{HALT}_9") (pintype "input"))
    )
    (net (code "33") (name "Net-(JP1-~{INT})") (class "Default")
      (node (ref "JP1") (pin "7") (pinfunction "~{INT}_7") (pintype "bidirectional"))
      (node (ref "JP2") (pin "7") (pinfunction "~{INT}_7") (pintype "bidirectional"))
      (node (ref "JP3") (pin "7") (pinfunction "~{INT}_7") (pintype "bidirectional"))
      (node (ref "JP4") (pin "7") (pinfunction "~{INT}_7") (pintype "bidirectional"))
      (node (ref "JP5") (pin "7") (pinfunction "~{INT}_7") (pintype "bidirectional"))
      (node (ref "JP6") (pin "7") (pinfunction "~{INT}_7") (pintype "bidirectional"))
    )
    (net (code "34") (name "Net-(JP1-~{IOREQ})") (class "Default")
      (node (ref "JP1") (pin "21") (pinfunction "~{IOREQ}_21") (pintype "output"))
      (node (ref "JP2") (pin "21") (pinfunction "~{IOREQ}_21") (pintype "output"))
      (node (ref "JP3") (pin "21") (pinfunction "~{IOREQ}_21") (pintype "output"))
      (node (ref "JP4") (pin "21") (pinfunction "~{IOREQ}_21") (pintype "output"))
      (node (ref "JP5") (pin "21") (pinfunction "~{IOREQ}_21") (pintype "output"))
      (node (ref "JP6") (pin "21") (pinfunction "~{IOREQ}_21") (pintype "output"))
    )
    (net (code "35") (name "Net-(JP1-~{M1})") (class "Default")
      (node (ref "JP1") (pin "5") (pinfunction "~{M1}_5") (pintype "bidirectional"))
      (node (ref "JP2") (pin "5") (pinfunction "~{M1}_5") (pintype "bidirectional"))
      (node (ref "JP3") (pin "5") (pinfunction "~{M1}_5") (pintype "bidirectional"))
      (node (ref "JP4") (pin "5") (pinfunction "~{M1}_5") (pintype "bidirectional"))
      (node (ref "JP5") (pin "5") (pinfunction "~{M1}_5") (pintype "bidirectional"))
      (node (ref "JP6") (pin "5") (pinfunction "~{M1}_5") (pintype "bidirectional"))
    )
    (net (code "36") (name "Net-(JP1-~{MREQ})") (class "Default")
      (node (ref "JP1") (pin "19") (pinfunction "~{MREQ}_19") (pintype "output"))
      (node (ref "JP2") (pin "19") (pinfunction "~{MREQ}_19") (pintype "output"))
      (node (ref "JP3") (pin "19") (pinfunction "~{MREQ}_19") (pintype "output"))
      (node (ref "JP4") (pin "19") (pinfunction "~{MREQ}_19") (pintype "output"))
      (node (ref "JP5") (pin "19") (pinfunction "~{MREQ}_19") (pintype "output"))
      (node (ref "JP6") (pin "19") (pinfunction "~{MREQ}_19") (pintype "output"))
    )
    (net (code "37") (name "Net-(JP1-~{NMI})") (class "Default")
      (node (ref "JP1") (pin "3") (pinfunction "~{NMI}_3") (pintype "bidirectional"))
      (node (ref "JP2") (pin "3") (pinfunction "~{NMI}_3") (pintype "bidirectional"))
      (node (ref "JP3") (pin "3") (pinfunction "~{NMI}_3") (pintype "bidirectional"))
      (node (ref "JP4") (pin "3") (pinfunction "~{NMI}_3") (pintype "bidirectional"))
      (node (ref "JP5") (pin "3") (pinfunction "~{NMI}_3") (pintype "bidirectional"))
      (node (ref "JP6") (pin "3") (pinfunction "~{NMI}_3") (pintype "bidirectional"))
    )
    (net (code "38") (name "Net-(JP1-~{RD})") (class "Default")
      (node (ref "JP1") (pin "25") (pinfunction "~{RD}_25") (pintype "output"))
      (node (ref "JP2") (pin "25") (pinfunction "~{RD}_25") (pintype "output"))
      (node (ref "JP3") (pin "25") (pinfunction "~{RD}_25") (pintype "output"))
      (node (ref "JP4") (pin "25") (pinfunction "~{RD}_25") (pintype "output"))
      (node (ref "JP5") (pin "25") (pinfunction "~{RD}_25") (pintype "output"))
      (node (ref "JP6") (pin "25") (pinfunction "~{RD}_25") (pintype "output"))
    )
    (net (code "39") (name "Net-(JP1-~{RESET})") (class "Default")
      (node (ref "JP1") (pin "1") (pinfunction "~{RESET}_1") (pintype "bidirectional"))
      (node (ref "JP2") (pin "1") (pinfunction "~{RESET}_1") (pintype "bidirectional"))
      (node (ref "JP3") (pin "1") (pinfunction "~{RESET}_1") (pintype "bidirectional"))
      (node (ref "JP4") (pin "1") (pinfunction "~{RESET}_1") (pintype "bidirectional"))
      (node (ref "JP5") (pin "1") (pinfunction "~{RESET}_1") (pintype "bidirectional"))
      (node (ref "JP6") (pin "1") (pinfunction "~{RESET}_1") (pintype "bidirectional"))
      (node (ref "MAX811") (pin "2") (pinfunction "~{RESET}_2") (pintype "output"))
    )
    (net (code "40") (name "Net-(JP1-~{WAIT})") (class "Default")
      (node (ref "JP1") (pin "15") (pinfunction "~{WAIT}_15") (pintype "input"))
      (node (ref "JP2") (pin "15") (pinfunction "~{WAIT}_15") (pintype "input"))
      (node (ref "JP3") (pin "15") (pinfunction "~{WAIT}_15") (pintype "input"))
      (node (ref "JP4") (pin "15") (pinfunction "~{WAIT}_15") (pintype "input"))
      (node (ref "JP5") (pin "15") (pinfunction "~{WAIT}_15") (pintype "input"))
      (node (ref "JP6") (pin "15") (pinfunction "~{WAIT}_15") (pintype "input"))
    )
    (net (code "41") (name "Net-(JP1-~{WR})") (class "Default")
      (node (ref "JP1") (pin "23") (pinfunction "~{WR}_23") (pintype "output"))
      (node (ref "JP2") (pin "23") (pinfunction "~{WR}_23") (pintype "output"))
      (node (ref "JP3") (pin "23") (pinfunction "~{WR}_23") (pintype "output"))
      (node (ref "JP4") (pin "23") (pinfunction "~{WR}_23") (pintype "output"))
      (node (ref "JP5") (pin "23") (pinfunction "~{WR}_23") (pintype "output"))
      (node (ref "JP6") (pin "23") (pinfunction "~{WR}_23") (pintype "output"))
    )
    (net (code "42") (name "Net-(LED1-PadA)") (class "Default")
      (node (ref "LED1") (pin "A") (pinfunction "A_A") (pintype "passive"))
      (node (ref "R1") (pin "1") (pinfunction "1_1") (pintype "passive"))
    )
    (net (code "43") (name "VCC") (class "Default")
      (node (ref "C1") (pin "1") (pinfunction "1_1") (pintype "passive"))
      (node (ref "IC1") (pin "3") (pinfunction "VO_3") (pintype "passive"))
      (node (ref "JP1") (pin "27") (pinfunction "VCC_27") (pintype "power_in"))
      (node (ref "JP2") (pin "27") (pinfunction "VCC_27") (pintype "power_in"))
      (node (ref "JP3") (pin "27") (pinfunction "VCC_27") (pintype "power_in"))
      (node (ref "JP4") (pin "27") (pinfunction "VCC_27") (pintype "power_in"))
      (node (ref "JP5") (pin "27") (pinfunction "VCC_27") (pintype "power_in"))
      (node (ref "JP6") (pin "27") (pinfunction "VCC_27") (pintype "power_in"))
      (node (ref "MAX811") (pin "4") (pinfunction "VCC_4") (pintype "power_in"))
      (node (ref "R1") (pin "2") (pinfunction "2_2") (pintype "passive"))
    )
    (net (code "44") (name "unconnected-(J1-Pad2)") (class "Default")
      (node (ref "J1") (pin "2") (pinfunction "2_2") (pintype "passive"))
    )
    (net (code "45") (name "unconnected-(S1-P1-Pad4)") (class "Default")
      (node (ref "S1") (pin "4") (pinfunction "P1_4") (pintype "passive"))
    )
  )
)
